# SX1302.net
KiCad netlist of a schematic drawn in Altium Designer
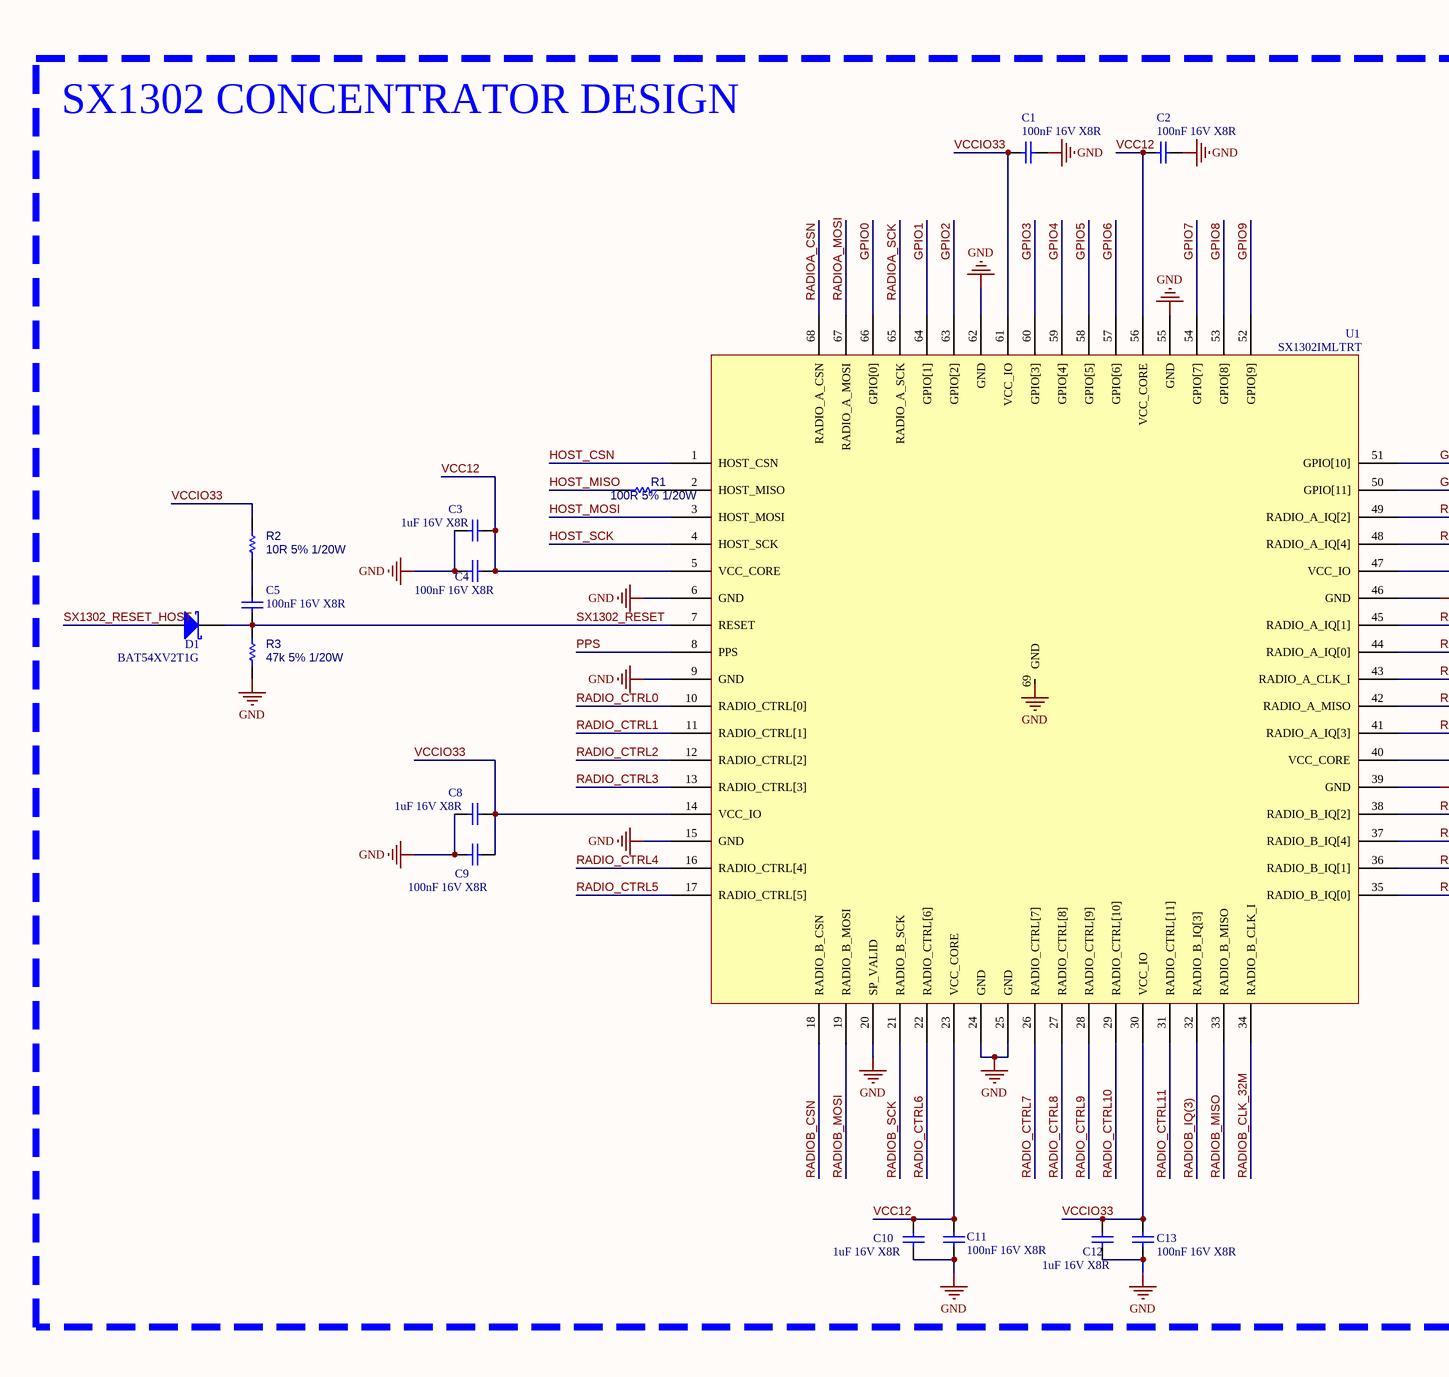
[diagram p0: SX1302.SchDoc, left]
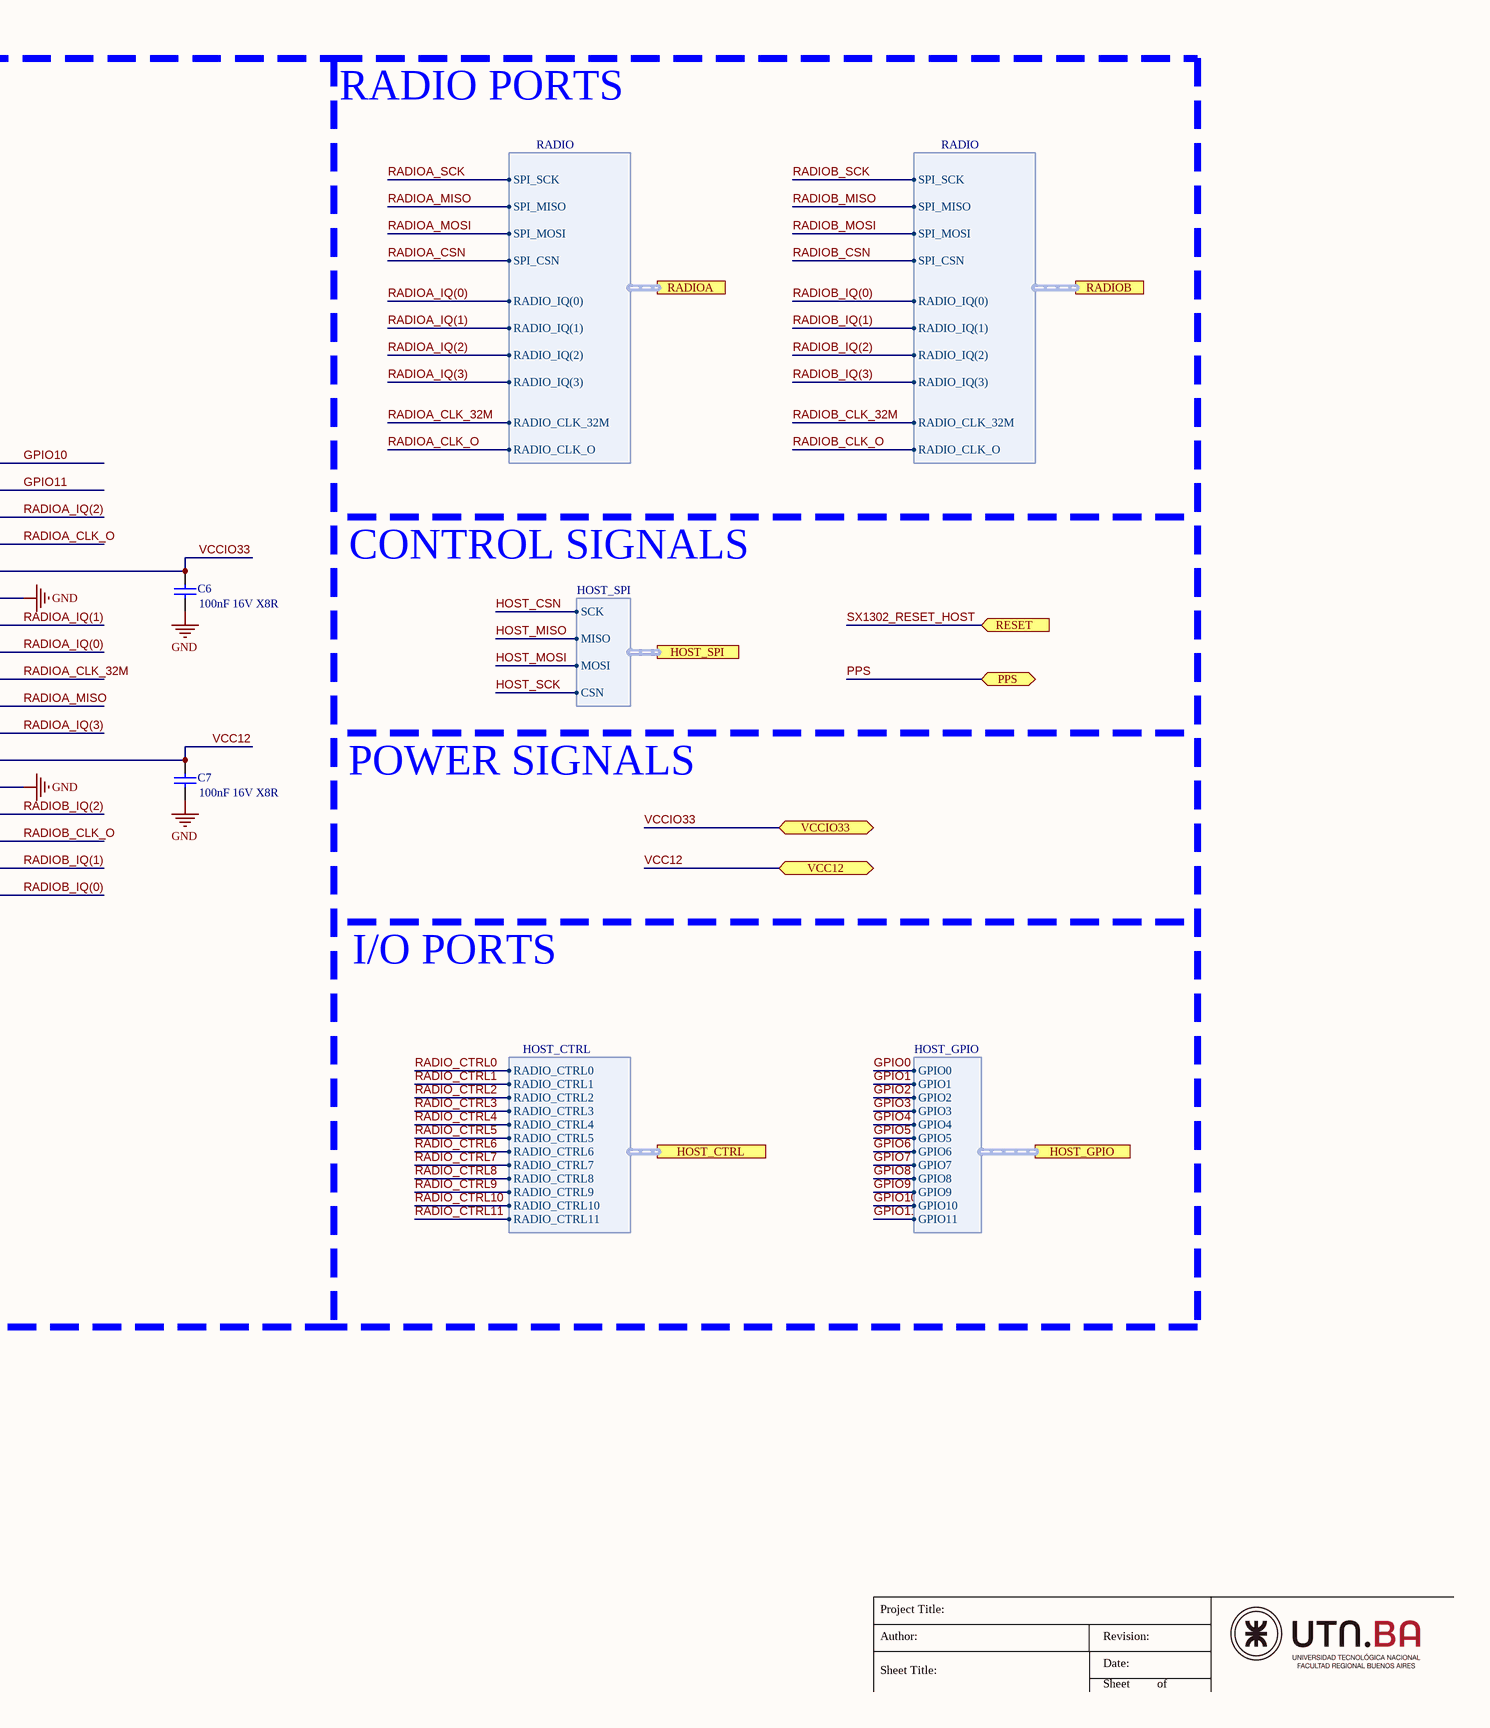
[diagram p1: SX1302.SchDoc, right]

(export (version "E")
  (design (tool "Eeschema 10.0.6"))
  (components
    (comp (ref "C1")
      (value "100nF 16V X8R")
      (footprint "C_0603")
      (description "Capacitor")
      (fields (field (name "MPN") "C1206C104K4HACAUTO") (field (name "MANUFACTURER") "KEMET"))
      (libsource (lib "lorawan_gateway") (part "Cap"))
    )
    (comp (ref "C2")
      (value "100nF 16V X8R")
      (footprint "C_0603")
      (description "Capacitor")
      (fields (field (name "MPN") "C1206C104K4HACAUTO") (field (name "MANUFACTURER") "KEMET"))
      (libsource (lib "lorawan_gateway") (part "Cap"))
    )
    (comp (ref "C3")
      (value "1uF 16V X8R")
      (footprint "C_0603")
      (description "Capacitor")
      (fields (field (name "MPN") "CGA4J3X8R1C105K125AB") (field (name "MANUFACTURER") "TDK Corporation"))
      (libsource (lib "lorawan_gateway") (part "Cap"))
    )
    (comp (ref "C4")
      (value "100nF 16V X8R")
      (footprint "C_0603")
      (description "Capacitor")
      (fields (field (name "MPN") "C1206C104K4HACAUTO") (field (name "MANUFACTURER") "KEMET"))
      (libsource (lib "lorawan_gateway") (part "Cap"))
    )
    (comp (ref "C5")
      (value "100nF 16V X8R")
      (footprint "C_0603")
      (description "Capacitor")
      (fields (field (name "MPN") "C1206C104K4HACAUTO") (field (name "MANUFACTURER") "KEMET"))
      (libsource (lib "lorawan_gateway") (part "Cap"))
    )
    (comp (ref "C6")
      (value "100nF 16V X8R")
      (footprint "C_0603")
      (description "Capacitor")
      (fields (field (name "MPN") "C1206C104K4HACAUTO") (field (name "MANUFACTURER") "KEMET"))
      (libsource (lib "lorawan_gateway") (part "Cap"))
    )
    (comp (ref "C7")
      (value "100nF 16V X8R")
      (footprint "C_0603")
      (description "Capacitor")
      (fields (field (name "MPN") "C1206C104K4HACAUTO") (field (name "MANUFACTURER") "KEMET"))
      (libsource (lib "lorawan_gateway") (part "Cap"))
    )
    (comp (ref "C8")
      (value "1uF 16V X8R")
      (footprint "C_0603")
      (description "Capacitor")
      (fields (field (name "MPN") "CGA4J3X8R1C105K125AB") (field (name "MANUFACTURER") "TDK Corporation"))
      (libsource (lib "lorawan_gateway") (part "Cap"))
    )
    (comp (ref "C9")
      (value "100nF 16V X8R")
      (footprint "C_0603")
      (description "Capacitor")
      (fields (field (name "MPN") "C1206C104K4HACAUTO") (field (name "MANUFACTURER") "KEMET"))
      (libsource (lib "lorawan_gateway") (part "Cap"))
    )
    (comp (ref "C10")
      (value "1uF 16V X8R")
      (footprint "C_0603")
      (description "Capacitor")
      (fields (field (name "MPN") "CGA4J3X8R1C105K125AB") (field (name "MANUFACTURER") "TDK Corporation"))
      (libsource (lib "lorawan_gateway") (part "Cap"))
    )
    (comp (ref "C11")
      (value "100nF 16V X8R")
      (footprint "C_0603")
      (description "Capacitor")
      (fields (field (name "MPN") "C1206C104K4HACAUTO") (field (name "MANUFACTURER") "KEMET"))
      (libsource (lib "lorawan_gateway") (part "Cap"))
    )
    (comp (ref "C12")
      (value "1uF 16V X8R")
      (footprint "C_0603")
      (description "Capacitor")
      (fields (field (name "MPN") "CGA4J3X8R1C105K125AB") (field (name "MANUFACTURER") "TDK Corporation"))
      (libsource (lib "lorawan_gateway") (part "Cap"))
    )
    (comp (ref "C13")
      (value "100nF 16V X8R")
      (footprint "C_0603")
      (description "Capacitor")
      (fields (field (name "MPN") "C1206C104K4HACAUTO") (field (name "MANUFACTURER") "KEMET"))
      (libsource (lib "lorawan_gateway") (part "Cap"))
    )
    (comp (ref "D1")
      (value "BAT54XV2T1G")
      (footprint "SOD-523")
      (description "DIODE SCHOTTKY 30V 200MA SOD523")
      (fields (field (name "MANUFACTURER") "onsemi"))
      (libsource (lib "lorawan_gateway") (part "D Schottky"))
    )
    (comp (ref "R1")
      (value "100R 5% 1/20W")
      (footprint "0603[1608]")
      (description "Resistor")
      (fields (field (name "MANUFACTURER") "Stackpole") (field (name "MPN") "RMCF0201JT100R"))
      (libsource (lib "lorawan_gateway") (part "Res"))
    )
    (comp (ref "R2")
      (value "10R 5% 1/20W")
      (footprint "0603[1608]")
      (description "Resistor")
      (fields (field (name "MANUFACTURER") "CH0402-10RJFPT") (field (name "MPN") "Vishay"))
      (libsource (lib "lorawan_gateway") (part "Res"))
    )
    (comp (ref "R3")
      (value "47k 5% 1/20W")
      (footprint "0603[1608]")
      (description "Resistor")
      (fields (field (name "MANUFACTURER") "Vishay") (field (name "MPN") "M55342K11B47K0MT1V"))
      (libsource (lib "lorawan_gateway") (part "Res"))
    )
    (comp (ref "U1")
      (value "SX1302IMLTRT")
      (footprint "vqfn68_7x7mm")
      (description "LoRa Core™ Digital Baseband Chip for LoRaWAN network gateways")
      (fields (field (name "MANUFACTURER") "Semtech"))
      (libsource (lib "lorawan_gateway") (part "SX1302"))
    )
  )
  (nets
    (net (code "5") (name "/GPIO0") (class "Default")
      (node (ref "U1") (pin "66") (pinfunction "GPIO[0]_66") (pintype "passive"))
    )
    (net (code "6") (name "/GPIO1") (class "Default")
      (node (ref "U1") (pin "64") (pinfunction "GPIO[1]_64") (pintype "passive"))
    )
    (net (code "7") (name "/GPIO2") (class "Default")
      (node (ref "U1") (pin "63") (pinfunction "GPIO[2]_63") (pintype "passive"))
    )
    (net (code "8") (name "/GPIO3") (class "Default")
      (node (ref "U1") (pin "60") (pinfunction "GPIO[3]_60") (pintype "passive"))
    )
    (net (code "9") (name "/GPIO4") (class "Default")
      (node (ref "U1") (pin "59") (pinfunction "GPIO[4]_59") (pintype "passive"))
    )
    (net (code "10") (name "/GPIO5") (class "Default")
      (node (ref "U1") (pin "58") (pinfunction "GPIO[5]_58") (pintype "passive"))
    )
    (net (code "11") (name "/GPIO6") (class "Default")
      (node (ref "U1") (pin "57") (pinfunction "GPIO[6]_57") (pintype "passive"))
    )
    (net (code "12") (name "/GPIO7") (class "Default")
      (node (ref "U1") (pin "54") (pinfunction "GPIO[7]_54") (pintype "passive"))
    )
    (net (code "13") (name "/GPIO8") (class "Default")
      (node (ref "U1") (pin "53") (pinfunction "GPIO[8]_53") (pintype "passive"))
    )
    (net (code "14") (name "/GPIO9") (class "Default")
      (node (ref "U1") (pin "52") (pinfunction "GPIO[9]_52") (pintype "passive"))
    )
    (net (code "15") (name "/GPIO10") (class "Default")
      (node (ref "U1") (pin "51") (pinfunction "GPIO[10]_51") (pintype "passive"))
    )
    (net (code "16") (name "/GPIO11") (class "Default")
      (node (ref "U1") (pin "50") (pinfunction "GPIO[11]_50") (pintype "passive"))
    )
    (net (code "17") (name "/HOST_CSN") (class "Default")
      (node (ref "U1") (pin "1") (pinfunction "HOST_CSN_1") (pintype "passive"))
    )
    (net (code "18") (name "/HOST_MISO") (class "Default")
      (node (ref "R1") (pin "2") (pinfunction "2_2") (pintype "passive"))
    )
    (net (code "19") (name "/HOST_MOSI") (class "Default")
      (node (ref "U1") (pin "3") (pinfunction "HOST_MOSI_3") (pintype "passive"))
    )
    (net (code "20") (name "/HOST_SCK") (class "Default")
      (node (ref "U1") (pin "4") (pinfunction "HOST_SCK_4") (pintype "passive"))
    )
    (net (code "21") (name "/PPS") (class "Default")
      (node (ref "U1") (pin "8") (pinfunction "PPS_8") (pintype "passive"))
    )
    (net (code "22") (name "/RADIOA_CLK_32M") (class "Default")
      (node (ref "U1") (pin "43") (pinfunction "RADIO_A_CLK_I_43") (pintype "passive"))
    )
    (net (code "23") (name "/RADIOA_CLK_O") (class "Default")
      (node (ref "U1") (pin "48") (pinfunction "RADIO_A_IQ[4]_48") (pintype "passive"))
    )
    (net (code "24") (name "/RADIOA_CSN") (class "Default")
      (node (ref "U1") (pin "68") (pinfunction "RADIO_A_CSN_68") (pintype "passive"))
    )
    (net (code "25") (name "/RADIOA_IQ(0)") (class "Default")
      (node (ref "U1") (pin "44") (pinfunction "RADIO_A_IQ[0]_44") (pintype "passive"))
    )
    (net (code "26") (name "/RADIOA_IQ(1)") (class "Default")
      (node (ref "U1") (pin "45") (pinfunction "RADIO_A_IQ[1]_45") (pintype "passive"))
    )
    (net (code "27") (name "/RADIOA_IQ(2)") (class "Default")
      (node (ref "U1") (pin "49") (pinfunction "RADIO_A_IQ[2]_49") (pintype "passive"))
    )
    (net (code "28") (name "/RADIOA_IQ(3)") (class "Default")
      (node (ref "U1") (pin "41") (pinfunction "RADIO_A_IQ[3]_41") (pintype "passive"))
    )
    (net (code "29") (name "/RADIOA_MISO") (class "Default")
      (node (ref "U1") (pin "42") (pinfunction "RADIO_A_MISO_42") (pintype "passive"))
    )
    (net (code "30") (name "/RADIOA_MOSI") (class "Default")
      (node (ref "U1") (pin "67") (pinfunction "RADIO_A_MOSI_67") (pintype "passive"))
    )
    (net (code "31") (name "/RADIOA_SCK") (class "Default")
      (node (ref "U1") (pin "65") (pinfunction "RADIO_A_SCK_65") (pintype "passive"))
    )
    (net (code "32") (name "/RADIOB_CLK_32M") (class "Default")
      (node (ref "U1") (pin "34") (pinfunction "RADIO_B_CLK_I_34") (pintype "passive"))
    )
    (net (code "33") (name "/RADIOB_CLK_O") (class "Default")
      (node (ref "U1") (pin "37") (pinfunction "RADIO_B_IQ[4]_37") (pintype "passive"))
    )
    (net (code "34") (name "/RADIOB_CSN") (class "Default")
      (node (ref "U1") (pin "18") (pinfunction "RADIO_B_CSN_18") (pintype "passive"))
    )
    (net (code "35") (name "/RADIOB_IQ(0)") (class "Default")
      (node (ref "U1") (pin "35") (pinfunction "RADIO_B_IQ[0]_35") (pintype "passive"))
    )
    (net (code "36") (name "/RADIOB_IQ(1)") (class "Default")
      (node (ref "U1") (pin "36") (pinfunction "RADIO_B_IQ[1]_36") (pintype "passive"))
    )
    (net (code "37") (name "/RADIOB_IQ(2)") (class "Default")
      (node (ref "U1") (pin "38") (pinfunction "RADIO_B_IQ[2]_38") (pintype "passive"))
    )
    (net (code "38") (name "/RADIOB_IQ(3)") (class "Default")
      (node (ref "U1") (pin "32") (pinfunction "RADIO_B_IQ[3]_32") (pintype "passive"))
    )
    (net (code "39") (name "/RADIOB_MISO") (class "Default")
      (node (ref "U1") (pin "33") (pinfunction "RADIO_B_MISO_33") (pintype "passive"))
    )
    (net (code "40") (name "/RADIOB_MOSI") (class "Default")
      (node (ref "U1") (pin "19") (pinfunction "RADIO_B_MOSI_19") (pintype "passive"))
    )
    (net (code "41") (name "/RADIOB_SCK") (class "Default")
      (node (ref "U1") (pin "21") (pinfunction "RADIO_B_SCK_21") (pintype "passive"))
    )
    (net (code "42") (name "/RADIO_CTRL0") (class "Default")
      (node (ref "U1") (pin "10") (pinfunction "RADIO_CTRL[0]_10") (pintype "passive"))
    )
    (net (code "43") (name "/RADIO_CTRL1") (class "Default")
      (node (ref "U1") (pin "11") (pinfunction "RADIO_CTRL[1]_11") (pintype "passive"))
    )
    (net (code "44") (name "/RADIO_CTRL2") (class "Default")
      (node (ref "U1") (pin "12") (pinfunction "RADIO_CTRL[2]_12") (pintype "passive"))
    )
    (net (code "45") (name "/RADIO_CTRL3") (class "Default")
      (node (ref "U1") (pin "13") (pinfunction "RADIO_CTRL[3]_13") (pintype "passive"))
    )
    (net (code "46") (name "/RADIO_CTRL4") (class "Default")
      (node (ref "U1") (pin "16") (pinfunction "RADIO_CTRL[4]_16") (pintype "passive"))
    )
    (net (code "47") (name "/RADIO_CTRL5") (class "Default")
      (node (ref "U1") (pin "17") (pinfunction "RADIO_CTRL[5]_17") (pintype "passive"))
    )
    (net (code "48") (name "/RADIO_CTRL6") (class "Default")
      (node (ref "U1") (pin "22") (pinfunction "RADIO_CTRL[6]_22") (pintype "passive"))
    )
    (net (code "49") (name "/RADIO_CTRL7") (class "Default")
      (node (ref "U1") (pin "26") (pinfunction "RADIO_CTRL[7]_26") (pintype "passive"))
    )
    (net (code "50") (name "/RADIO_CTRL8") (class "Default")
      (node (ref "U1") (pin "27") (pinfunction "RADIO_CTRL[8]_27") (pintype "passive"))
    )
    (net (code "51") (name "/RADIO_CTRL9") (class "Default")
      (node (ref "U1") (pin "28") (pinfunction "RADIO_CTRL[9]_28") (pintype "passive"))
    )
    (net (code "52") (name "/RADIO_CTRL10") (class "Default")
      (node (ref "U1") (pin "29") (pinfunction "RADIO_CTRL[10]_29") (pintype "passive"))
    )
    (net (code "53") (name "/RADIO_CTRL11") (class "Default")
      (node (ref "U1") (pin "31") (pinfunction "RADIO_CTRL[11]_31") (pintype "passive"))
    )
    (net (code "54") (name "/SX1302_RESET") (class "Default")
      (node (ref "C5") (pin "1") (pinfunction "1_1") (pintype "passive"))
      (node (ref "D1") (pin "1") (pinfunction "K_1") (pintype "passive"))
      (node (ref "R3") (pin "2") (pinfunction "2_2") (pintype "passive"))
      (node (ref "U1") (pin "7") (pinfunction "RESET_7") (pintype "passive"))
    )
    (net (code "55") (name "/SX1302_RESET_HOST") (class "Default")
      (node (ref "D1") (pin "2") (pinfunction "A_2") (pintype "passive"))
    )
    (net (code "56") (name "/VCC12") (class "Default")
      (node (ref "C10") (pin "2") (pinfunction "2_2") (pintype "passive"))
      (node (ref "C11") (pin "2") (pinfunction "2_2") (pintype "passive"))
      (node (ref "C2") (pin "2") (pinfunction "2_2") (pintype "passive"))
      (node (ref "C3") (pin "2") (pinfunction "2_2") (pintype "passive"))
      (node (ref "C4") (pin "2") (pinfunction "2_2") (pintype "passive"))
      (node (ref "C7") (pin "2") (pinfunction "2_2") (pintype "passive"))
      (node (ref "U1") (pin "23") (pinfunction "VCC_CORE_23") (pintype "passive"))
      (node (ref "U1") (pin "40") (pinfunction "VCC_CORE_40") (pintype "passive"))
      (node (ref "U1") (pin "5") (pinfunction "VCC_CORE_5") (pintype "passive"))
      (node (ref "U1") (pin "56") (pinfunction "VCC_CORE_56") (pintype "passive"))
    )
    (net (code "57") (name "/VCCIO33") (class "Default")
      (node (ref "C1") (pin "2") (pinfunction "2_2") (pintype "passive"))
      (node (ref "C12") (pin "2") (pinfunction "2_2") (pintype "passive"))
      (node (ref "C13") (pin "2") (pinfunction "2_2") (pintype "passive"))
      (node (ref "C6") (pin "2") (pinfunction "2_2") (pintype "passive"))
      (node (ref "C8") (pin "2") (pinfunction "2_2") (pintype "passive"))
      (node (ref "C9") (pin "2") (pinfunction "2_2") (pintype "passive"))
      (node (ref "R2") (pin "2") (pinfunction "2_2") (pintype "passive"))
      (node (ref "U1") (pin "14") (pinfunction "VCC_IO_14") (pintype "passive"))
      (node (ref "U1") (pin "30") (pinfunction "VCC_IO_30") (pintype "passive"))
      (node (ref "U1") (pin "47") (pinfunction "VCC_IO_47") (pintype "passive"))
      (node (ref "U1") (pin "61") (pinfunction "VCC_IO_61") (pintype "passive"))
    )
    (net (code "62") (name "GND") (class "Default")
      (node (ref "C1") (pin "1") (pinfunction "1_1") (pintype "passive"))
      (node (ref "C10") (pin "1") (pinfunction "1_1") (pintype "passive"))
      (node (ref "C11") (pin "1") (pinfunction "1_1") (pintype "passive"))
      (node (ref "C12") (pin "1") (pinfunction "1_1") (pintype "passive"))
      (node (ref "C13") (pin "1") (pinfunction "1_1") (pintype "passive"))
      (node (ref "C2") (pin "1") (pinfunction "1_1") (pintype "passive"))
      (node (ref "C3") (pin "1") (pinfunction "1_1") (pintype "passive"))
      (node (ref "C4") (pin "1") (pinfunction "1_1") (pintype "passive"))
      (node (ref "C6") (pin "1") (pinfunction "1_1") (pintype "passive"))
      (node (ref "C7") (pin "1") (pinfunction "1_1") (pintype "passive"))
      (node (ref "C8") (pin "1") (pinfunction "1_1") (pintype "passive"))
      (node (ref "C9") (pin "1") (pinfunction "1_1") (pintype "passive"))
      (node (ref "R3") (pin "1") (pinfunction "1_1") (pintype "passive"))
      (node (ref "U1") (pin "15") (pinfunction "GND_15") (pintype "power_in"))
      (node (ref "U1") (pin "20") (pinfunction "SP_VALID_20") (pintype "passive"))
      (node (ref "U1") (pin "24") (pinfunction "GND_24") (pintype "power_in"))
      (node (ref "U1") (pin "25") (pinfunction "GND_25") (pintype "power_in"))
      (node (ref "U1") (pin "39") (pinfunction "GND_39") (pintype "power_in"))
      (node (ref "U1") (pin "46") (pinfunction "GND_46") (pintype "power_in"))
      (node (ref "U1") (pin "55") (pinfunction "GND_55") (pintype "power_in"))
      (node (ref "U1") (pin "6") (pinfunction "GND_6") (pintype "power_in"))
      (node (ref "U1") (pin "62") (pinfunction "GND_62") (pintype "power_in"))
      (node (ref "U1") (pin "69") (pinfunction "GND_69") (pintype "power_in"))
      (node (ref "U1") (pin "9") (pinfunction "GND_9") (pintype "power_in"))
    )
    (net (code "63") (name "Net-(C5-Pad2)") (class "Default")
      (node (ref "C5") (pin "2") (pinfunction "2_2") (pintype "passive"))
      (node (ref "R2") (pin "1") (pinfunction "1_1") (pintype "passive"))
    )
    (net (code "64") (name "Net-(U1-HOST_MISO)") (class "Default")
      (node (ref "R1") (pin "1") (pinfunction "1_1") (pintype "passive"))
      (node (ref "U1") (pin "2") (pinfunction "HOST_MISO_2") (pintype "passive"))
    )
  )
)
